# Payload_Development_Kit.net
KiCad netlist of a schematic drawn in Altium Designer
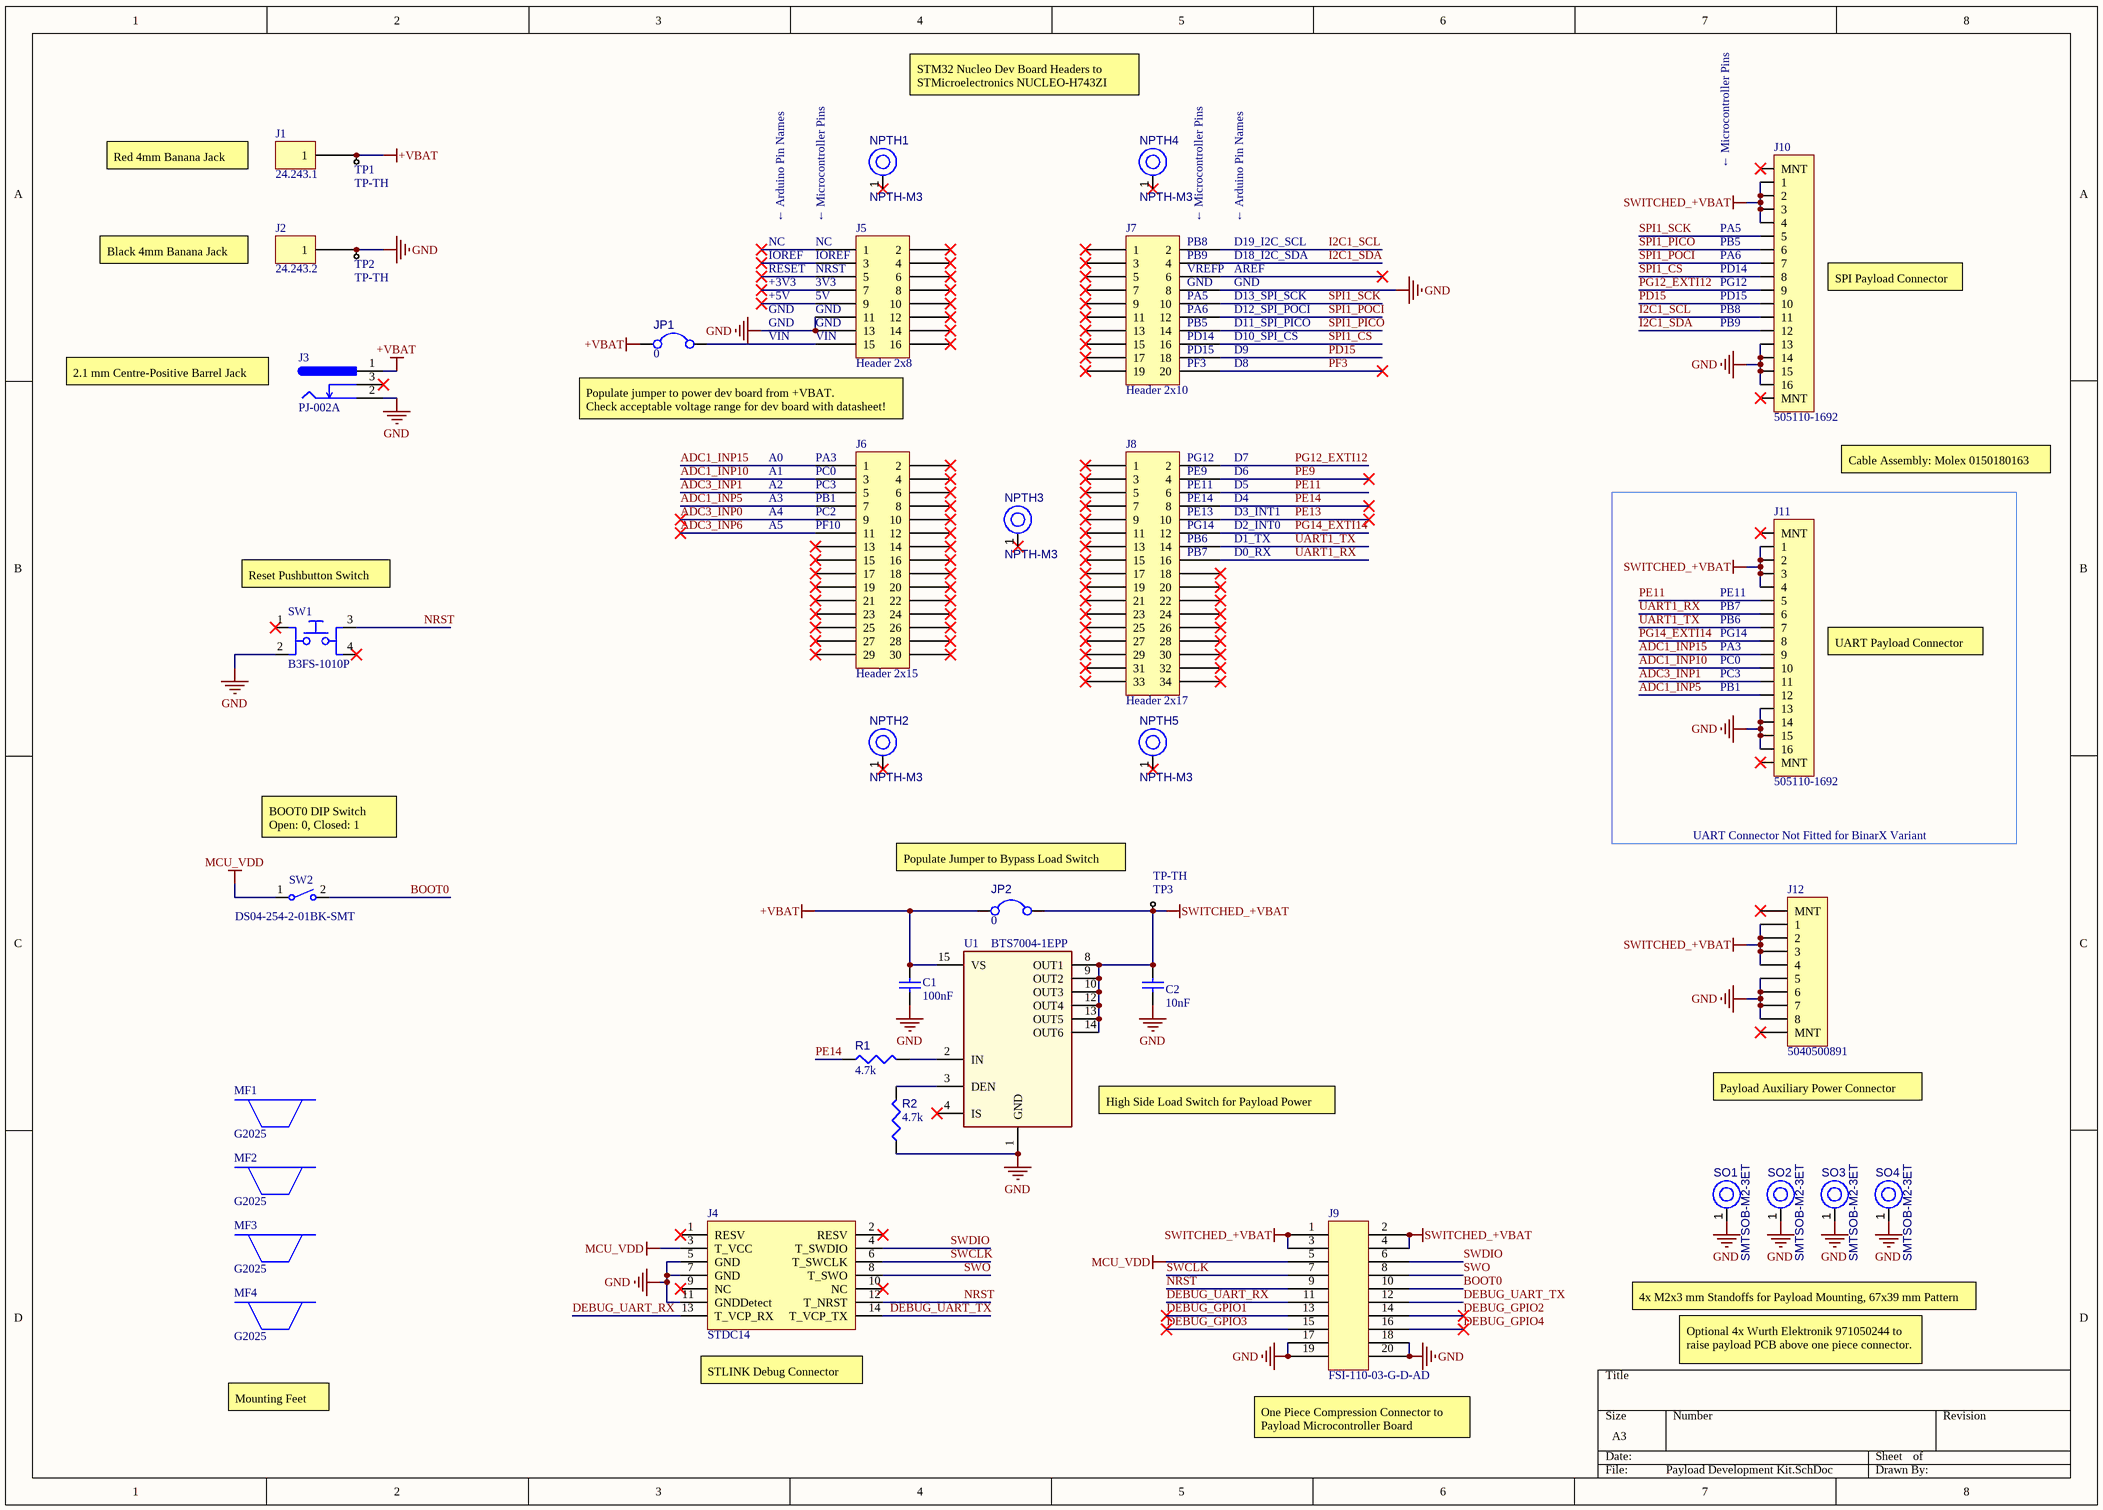
[diagram p0: Payload Development Kit.SchDoc]

(export (version "E")
  (design (tool "Eeschema 10.0.6"))
  (components
    (comp (ref "C1")
      (value "100nF")
      (footprint "CAPC1608X90X40ML10T20")
      (description "Chip Capacitor, 100 nF, +/- 10%, 50 V, 0603 (1608 Metric)")
      (fields (field (name "TOLERANCE") "10%") (field (name "Comment") "Capacitor 100 nF +/-10% 50 V 0603"))
      (libsource (lib "Binar Space Program - Curtin University") (part "CAP-NP-2"))
    )
    (comp (ref "C2")
      (value "10nF")
      (footprint "CAPC1608X90X40NL10T20")
      (description "Chip Capacitor, 10 nF, +/- 10%, 50 V, 0603 (1608 Metric)")
      (fields
        (field (name "TOLERANCE") "10%")
        (field (name "Comment") "Capacitor 10 nF +/-10% 50 V 0603")
        (field (name "CREATED BY") "Robert Howie")
      )
      (libsource (lib "Binar Space Program - Curtin University") (part "CAP-NP-2"))
    )
    (comp (ref "J1")
      (value "24.243.1")
      (footprint "FP-24_243_1-MFG")
      (description "Banana Test Connector, 4mm, Socket, PCB Mount, 24 A, 60 VDC, Silver Plated Contacts, Red")
      (fields (field (name "SOURCE") "Spacecraft Emulator Nucleo-144 Shield.SCHLIB"))
      (libsource (lib "Binar Space Program - Curtin University") (part "24.243.1"))
    )
    (comp (ref "J2")
      (value "24.243.2")
      (footprint "FP-24_243_2-MFG")
      (description "Banana Test Connector, 4mm, Socket, PCB Mount, 24 A, 60 VDC, Silver Plated Contacts, Black")
      (fields (field (name "SOURCE") "Spacecraft Emulator Nucleo-144 Shield.SCHLIB"))
      (libsource (lib "Binar Space Program - Curtin University") (part "24.243.2"))
    )
    (comp (ref "J3")
      (value "PJ-002A")
      (footprint "CUI-PJ-002A_V")
      (description "2.1mm Dia Centre Pin, 5.5mm barrel, 24V, 2.5A")
      (libsource (lib "Binar Space Program - Curtin University") (part "Barrel Jack with NC Insertion Switch"))
    )
    (comp (ref "J4")
      (value "STDC14")
      (footprint "FP-FTSH-107-01-L-DV-K")
      (description "STDC14 for STLINK Programmer")
      (libsource (lib "Binar Space Program - Curtin University") (part "STDC14"))
    )
    (comp (ref "J5")
      (value "Header 2x8")
      (footprint "SAMTEC_SSW-108-01-T-D")
      (fields (field (name "SOURCE") "Spacecraft Emulator Nucleo-144 Shield.SCHLIB"))
      (libsource (lib "Binar Space Program - Curtin University") (part "CMP-002-00019-12"))
    )
    (comp (ref "J6")
      (value "Header 2x15")
      (footprint "SAMTEC_SSW-115-01-T-D")
      (fields (field (name "SOURCE") "Spacecraft Emulator Nucleo-144 Shield.SCHLIB"))
      (libsource (lib "Binar Space Program - Curtin University") (part "CMP-002-00020-6"))
    )
    (comp (ref "J7")
      (value "Header 2x10")
      (footprint "SAMTEC_SSW-110-01-T-D")
      (fields (field (name "SOURCE") "Spacecraft Emulator Nucleo-144 Shield.SCHLIB"))
      (libsource (lib "Binar Space Program - Curtin University") (part "CMP-002-00021-9"))
    )
    (comp (ref "J8")
      (value "Header 2x17")
      (footprint "SAMTEC_SSW-117-01-T-D")
      (fields (field (name "SOURCE") "Spacecraft Emulator Nucleo-144 Shield.SCHLIB"))
      (libsource (lib "Binar Space Program - Curtin University") (part "CMP-002-00022-6"))
    )
    (comp (ref "J9")
      (value "FSI-110-03-G-D-AD")
      (footprint "SAMTEC_FSI-110-03-X-D-AD-TR")
      (description "20 Position, 2 Row, 1mm Pich One Piece Connector, SMD, Samtec FSI-110-03-G-D-AD")
      (libsource (lib "Binar Space Program - Curtin University") (part "CMP-002-00071-3"))
    )
    (comp (ref "J10")
      (value "505110-1692")
      (footprint "FP-505110-1692-MFG")
      (description "Conn FFC/FPC Connector SKT 16 POS 0.5mm Solder RA SMD Easy-On™ T/R")
      (fields (field (name "SOURCE") "Spacecraft Emulator Nucleo-144 Shield.SCHLIB"))
      (libsource (lib "Binar Space Program - Curtin University") (part "CMP-002-00072-15"))
    )
    (comp (ref "J11")
      (value "505110-1692")
      (footprint "FP-505110-1692-MFG")
      (description "Conn FFC/FPC Connector SKT 16 POS 0.5mm Solder RA SMD Easy-On™ T/R")
      (fields (field (name "SOURCE") "Spacecraft Emulator Nucleo-144 Shield.SCHLIB"))
      (libsource (lib "Binar Space Program - Curtin University") (part "CMP-002-00072-15"))
    )
    (comp (ref "J12")
      (value "5040500891")
      (footprint "CON_5040500891")
      (libsource (lib "Binar Space Program - Curtin University") (part "CMP-002-00075-1"))
    )
    (comp (ref "JP1")
      (value "0")
      (footprint "RESC1608X55X25ML10T15")
      (description "Jumper 0603")
      (fields (field (name "Comment") "CMP-009-00177-3"))
      (libsource (lib "Binar Space Program - Curtin University") (part "CMP-009-00177-3"))
    )
    (comp (ref "JP2")
      (value "0")
      (footprint "RESC1608X55X25ML10T15")
      (description "28A Jumper 0603")
      (fields (field (name "Comment") "26A 0603 Jumper"))
      (libsource (lib "Binar Space Program - Curtin University") (part "CMP-009-00177-3"))
    )
    (comp (ref "MF1")
      (value "G2025")
      (footprint "New footprint 1")
      (description "Rubber Push-In Bumper Ø12.7 mm by 12.7 mm high")
      (libsource (lib "Binar Space Program - Curtin University") (part "New symbol 1"))
    )
    (comp (ref "MF2")
      (value "G2025")
      (footprint "New footprint 1")
      (description "Rubber Push-In Bumper Ø12.7 mm by 12.7 mm high")
      (libsource (lib "Binar Space Program - Curtin University") (part "New symbol 1"))
    )
    (comp (ref "MF3")
      (value "G2025")
      (footprint "New footprint 1")
      (description "Rubber Push-In Bumper Ø12.7 mm by 12.7 mm high")
      (libsource (lib "Binar Space Program - Curtin University") (part "New symbol 1"))
    )
    (comp (ref "MF4")
      (value "G2025")
      (footprint "New footprint 1")
      (description "Rubber Push-In Bumper Ø12.7 mm by 12.7 mm high")
      (libsource (lib "Binar Space Program - Curtin University") (part "New symbol 1"))
    )
    (comp (ref "NPTH1")
      (value "NPTH-M3")
      (footprint "NPTH-M3")
      (description "M3 Non-Plated Through Hole")
      (fields (field (name "SOURCE") "Spacecraft Emulator Nucleo-144 Shield.SCHLIB"))
      (libsource (lib "Binar Space Program - Curtin University") (part "CMP-00028-00015-4"))
    )
    (comp (ref "NPTH2")
      (value "NPTH-M3")
      (footprint "NPTH-M3")
      (description "M3 Non-Plated Through Hole")
      (fields (field (name "SOURCE") "Spacecraft Emulator Nucleo-144 Shield.SCHLIB"))
      (libsource (lib "Binar Space Program - Curtin University") (part "CMP-00028-00015-4"))
    )
    (comp (ref "NPTH3")
      (value "NPTH-M3")
      (footprint "NPTH-M3")
      (description "M3 Non-Plated Through Hole")
      (fields (field (name "SOURCE") "Spacecraft Emulator Nucleo-144 Shield.SCHLIB"))
      (libsource (lib "Binar Space Program - Curtin University") (part "CMP-00028-00015-4"))
    )
    (comp (ref "NPTH4")
      (value "NPTH-M3")
      (footprint "NPTH-M3")
      (description "M3 Non-Plated Through Hole")
      (fields (field (name "SOURCE") "Spacecraft Emulator Nucleo-144 Shield.SCHLIB"))
      (libsource (lib "Binar Space Program - Curtin University") (part "CMP-00028-00015-4"))
    )
    (comp (ref "NPTH5")
      (value "NPTH-M3")
      (footprint "NPTH-M3")
      (description "M3 Non-Plated Through Hole")
      (fields (field (name "SOURCE") "Spacecraft Emulator Nucleo-144 Shield.SCHLIB"))
      (libsource (lib "Binar Space Program - Curtin University") (part "CMP-00028-00015-4"))
    )
    (comp (ref "R1")
      (value "4.7k")
      (footprint "RESC1608X55X25ML10T15")
      (description "Chip Resistor, 4.7 KOhm, +/- 1%, 0.1 W, -55 to 155 degC, 0603 (1608 Metric)")
      (fields
        (field (name "TOLERANCE") "1%")
        (field (name "POWER") "100mW")
        (field (name "CREATED BY") "Robert Howie")
      )
      (libsource (lib "Binar Space Program - Curtin University") (part "RES-2"))
    )
    (comp (ref "R2")
      (value "4.7k")
      (footprint "RESC1608X55X25ML10T15")
      (description "Chip Resistor, 4.7 KOhm, +/- 1%, 0.1 W, -55 to 155 degC, 0603 (1608 Metric)")
      (fields
        (field (name "TOLERANCE") "1%")
        (field (name "POWER") "100mW")
        (field (name "CREATED BY") "Robert Howie")
      )
      (libsource (lib "Binar Space Program - Curtin University") (part "RES-2"))
    )
    (comp (ref "SO1")
      (value "SMTSOB-M2-3ET")
      (footprint "SMTSOB-M2-3ET")
      (description "M2x3mm SMD Standoff, Brass")
      (libsource (lib "Binar Space Program - Curtin University") (part "CMP-00028-00008-1"))
    )
    (comp (ref "SO2")
      (value "SMTSOB-M2-3ET")
      (footprint "SMTSOB-M2-3ET")
      (description "M2x3mm SMD Standoff, Brass")
      (libsource (lib "Binar Space Program - Curtin University") (part "CMP-00028-00008-1"))
    )
    (comp (ref "SO3")
      (value "SMTSOB-M2-3ET")
      (footprint "SMTSOB-M2-3ET")
      (description "M2x3mm SMD Standoff, Brass")
      (libsource (lib "Binar Space Program - Curtin University") (part "CMP-00028-00008-1"))
    )
    (comp (ref "SO4")
      (value "SMTSOB-M2-3ET")
      (footprint "SMTSOB-M2-3ET")
      (description "M2x3mm SMD Standoff, Brass")
      (libsource (lib "Binar Space Program - Curtin University") (part "CMP-00028-00008-1"))
    )
    (comp (ref "SW1")
      (value "B3FS-1010P")
      (footprint "B3FS-1010P-Footprint-1")
      (libsource (lib "Binar Space Program - Curtin University") (part "SW-SPST-NO-4"))
    )
    (comp (ref "SW2")
      (value "DS04-254-2-01BK-SMT")
      (footprint "SW_DS04-254-1-01BK-SMT")
      (description "DIP Switch")
      (libsource (lib "Binar Space Program - Curtin University") (part "SW-SPST-2_C"))
    )
    (comp (ref "TP1")
      (value "TP-TH")
      (footprint "1 Pin Header Strip Footprint")
      (description "Throughole Test Point")
      (fields (field (name "CREATED BY") "Robert Howie"))
      (libsource (lib "Binar Space Program - Curtin University") (part "CMP-001-0001-5"))
    )
    (comp (ref "TP2")
      (value "TP-TH")
      (footprint "1 Pin Header Strip Footprint")
      (description "Throughole Test Point")
      (fields (field (name "CREATED BY") "Robert Howie"))
      (libsource (lib "Binar Space Program - Curtin University") (part "CMP-001-0001-5"))
    )
    (comp (ref "TP3")
      (value "TP-TH")
      (footprint "1 Pin Header Strip Footprint")
      (description "Throughole Test Point")
      (fields (field (name "CREATED BY") "Robert Howie"))
      (libsource (lib "Binar Space Program - Curtin University") (part "CMP-001-0001-5"))
    )
    (comp (ref "U1")
      (value "BTS7004-1EPP")
      (footprint "SOP65P600X105-15N-1-V")
      (description "Smart High-Side Power Switch, 1x4 mΩ")
      (fields (field (name "MANUFACTURER") "Infineon Technologies"))
      (libsource (lib "Binar Space Program - Curtin University") (part "BTS7004-1EPP"))
    )
  )
  (nets
    (net (code "1") (name "+VBAT") (class "Default")
      (node (ref "C1") (pin "1") (pinfunction "1_1") (pintype "passive"))
      (node (ref "J1") (pin "1") (pinfunction "1_1") (pintype "passive"))
      (node (ref "J1") (pin "2") (pinfunction "2_2") (pintype "passive"))
      (node (ref "J3") (pin "1") (pinfunction "1_1") (pintype "passive"))
      (node (ref "JP1") (pin "1") (pinfunction "1_1") (pintype "passive"))
      (node (ref "JP2") (pin "1") (pinfunction "1_1") (pintype "passive"))
      (node (ref "TP1") (pin "1") (pinfunction "TP_1") (pintype "passive"))
      (node (ref "U1") (pin "15") (pinfunction "VS_15") (pintype "passive"))
    )
    (net (code "2") (name "/ADC1_INP5") (class "Default")
      (node (ref "J11") (pin "12") (pinfunction "12_12") (pintype "passive"))
      (node (ref "J6") (pin "7") (pinfunction "7_7") (pintype "passive"))
    )
    (net (code "3") (name "/ADC1_INP10") (class "Default")
      (node (ref "J11") (pin "10") (pinfunction "10_10") (pintype "passive"))
      (node (ref "J6") (pin "3") (pinfunction "3_3") (pintype "passive"))
    )
    (net (code "4") (name "/ADC1_INP15") (class "Default")
      (node (ref "J11") (pin "9") (pinfunction "9_9") (pintype "passive"))
      (node (ref "J6") (pin "1") (pinfunction "1_1") (pintype "passive"))
    )
    (net (code "5") (name "/ADC3_INP0") (class "Default")
      (node (ref "J6") (pin "9") (pinfunction "9_9") (pintype "passive+no_connect"))
    )
    (net (code "6") (name "/ADC3_INP1") (class "Default")
      (node (ref "J11") (pin "11") (pinfunction "11_11") (pintype "passive"))
      (node (ref "J6") (pin "5") (pinfunction "5_5") (pintype "passive"))
    )
    (net (code "7") (name "/ADC3_INP6") (class "Default")
      (node (ref "J6") (pin "11") (pinfunction "11_11") (pintype "passive+no_connect"))
    )
    (net (code "8") (name "/BOOT0") (class "Default")
      (node (ref "J9") (pin "10") (pinfunction "10_10") (pintype "passive"))
      (node (ref "SW2") (pin "2") (pinfunction "2_2") (pintype "passive"))
    )
    (net (code "9") (name "/DEBUG_GPIO1") (class "Default")
      (node (ref "J9") (pin "13") (pinfunction "13_13") (pintype "passive+no_connect"))
    )
    (net (code "10") (name "/DEBUG_GPIO2") (class "Default")
      (node (ref "J9") (pin "14") (pinfunction "14_14") (pintype "passive+no_connect"))
    )
    (net (code "11") (name "/DEBUG_GPIO3") (class "Default")
      (node (ref "J9") (pin "15") (pinfunction "15_15") (pintype "passive+no_connect"))
    )
    (net (code "12") (name "/DEBUG_GPIO4") (class "Default")
      (node (ref "J9") (pin "16") (pinfunction "16_16") (pintype "passive+no_connect"))
    )
    (net (code "13") (name "/DEBUG_UART_RX") (class "Default")
      (node (ref "J4") (pin "13") (pinfunction "T_VCP_RX_13") (pintype "passive"))
      (node (ref "J9") (pin "11") (pinfunction "11_11") (pintype "passive"))
    )
    (net (code "14") (name "/DEBUG_UART_TX") (class "Default")
      (node (ref "J4") (pin "14") (pinfunction "T_VCP_TX_14") (pintype "passive"))
      (node (ref "J9") (pin "12") (pinfunction "12_12") (pintype "passive"))
    )
    (net (code "15") (name "/I2C1_SCL") (class "Default")
      (node (ref "J10") (pin "11") (pinfunction "11_11") (pintype "passive"))
      (node (ref "J7") (pin "2") (pinfunction "2_2") (pintype "passive"))
    )
    (net (code "16") (name "/I2C1_SDA") (class "Default")
      (node (ref "J10") (pin "12") (pinfunction "12_12") (pintype "passive"))
      (node (ref "J7") (pin "4") (pinfunction "4_4") (pintype "passive"))
    )
    (net (code "17") (name "/NRST") (class "Default")
      (node (ref "J4") (pin "12") (pinfunction "T_NRST_12") (pintype "passive"))
      (node (ref "J9") (pin "9") (pinfunction "9_9") (pintype "passive"))
      (node (ref "SW1") (pin "3") (pinfunction "3_3") (pintype "passive"))
    )
    (net (code "18") (name "/PD15") (class "Default")
      (node (ref "J10") (pin "10") (pinfunction "10_10") (pintype "passive"))
      (node (ref "J7") (pin "18") (pinfunction "18_18") (pintype "passive"))
    )
    (net (code "19") (name "/PE9") (class "Default")
      (node (ref "J8") (pin "4") (pinfunction "4_4") (pintype "passive+no_connect"))
    )
    (net (code "20") (name "/PE11") (class "Default")
      (node (ref "J11") (pin "5") (pinfunction "5_5") (pintype "passive"))
      (node (ref "J8") (pin "6") (pinfunction "6_6") (pintype "passive"))
    )
    (net (code "21") (name "/PE13") (class "Default")
      (node (ref "J8") (pin "10") (pinfunction "10_10") (pintype "passive+no_connect"))
    )
    (net (code "22") (name "/PE14") (class "Default")
      (node (ref "J8") (pin "8") (pinfunction "8_8") (pintype "passive"))
      (node (ref "R1") (pin "1") (pinfunction "1_1") (pintype "passive"))
    )
    (net (code "23") (name "/PF3") (class "Default")
      (node (ref "J7") (pin "20") (pinfunction "20_20") (pintype "passive+no_connect"))
    )
    (net (code "24") (name "/PG12_EXTI12") (class "Default")
      (node (ref "J10") (pin "9") (pinfunction "9_9") (pintype "passive"))
      (node (ref "J8") (pin "2") (pinfunction "2_2") (pintype "passive"))
    )
    (net (code "25") (name "/PG14_EXTI14") (class "Default")
      (node (ref "J11") (pin "8") (pinfunction "8_8") (pintype "passive"))
      (node (ref "J8") (pin "12") (pinfunction "12_12") (pintype "passive"))
    )
    (net (code "26") (name "/SPI1_CS") (class "Default")
      (node (ref "J10") (pin "8") (pinfunction "8_8") (pintype "passive"))
      (node (ref "J7") (pin "16") (pinfunction "16_16") (pintype "passive"))
    )
    (net (code "27") (name "/SPI1_PICO") (class "Default")
      (node (ref "J10") (pin "6") (pinfunction "6_6") (pintype "passive"))
      (node (ref "J7") (pin "14") (pinfunction "14_14") (pintype "passive"))
    )
    (net (code "28") (name "/SPI1_POCI") (class "Default")
      (node (ref "J10") (pin "7") (pinfunction "7_7") (pintype "passive"))
      (node (ref "J7") (pin "12") (pinfunction "12_12") (pintype "passive"))
    )
    (net (code "29") (name "/SPI1_SCK") (class "Default")
      (node (ref "J10") (pin "5") (pinfunction "5_5") (pintype "passive"))
      (node (ref "J7") (pin "10") (pinfunction "10_10") (pintype "passive"))
    )
    (net (code "30") (name "/SWCLK") (class "Default")
      (node (ref "J4") (pin "6") (pinfunction "T_SWCLK_6") (pintype "passive"))
      (node (ref "J9") (pin "7") (pinfunction "7_7") (pintype "passive"))
    )
    (net (code "31") (name "/SWDIO") (class "Default")
      (node (ref "J4") (pin "4") (pinfunction "T_SWDIO_4") (pintype "passive"))
      (node (ref "J9") (pin "6") (pinfunction "6_6") (pintype "passive"))
    )
    (net (code "32") (name "/SWO") (class "Default")
      (node (ref "J4") (pin "8") (pinfunction "T_SWO_8") (pintype "passive"))
      (node (ref "J9") (pin "8") (pinfunction "8_8") (pintype "passive"))
    )
    (net (code "33") (name "/UART1_RX") (class "Default")
      (node (ref "J11") (pin "6") (pinfunction "6_6") (pintype "passive"))
      (node (ref "J8") (pin "16") (pinfunction "16_16") (pintype "passive"))
    )
    (net (code "34") (name "/UART1_TX") (class "Default")
      (node (ref "J11") (pin "7") (pinfunction "7_7") (pintype "passive"))
      (node (ref "J8") (pin "14") (pinfunction "14_14") (pintype "passive"))
    )
    (net (code "35") (name "GND") (class "Default")
      (node (ref "C1") (pin "2") (pinfunction "2_2") (pintype "passive"))
      (node (ref "C2") (pin "1") (pinfunction "1_1") (pintype "passive"))
      (node (ref "J10") (pin "13") (pinfunction "13_13") (pintype "passive"))
      (node (ref "J10") (pin "14") (pinfunction "14_14") (pintype "passive"))
      (node (ref "J10") (pin "15") (pinfunction "15_15") (pintype "passive"))
      (node (ref "J10") (pin "16") (pinfunction "16_16") (pintype "passive"))
      (node (ref "J11") (pin "13") (pinfunction "13_13") (pintype "passive"))
      (node (ref "J11") (pin "14") (pinfunction "14_14") (pintype "passive"))
      (node (ref "J11") (pin "15") (pinfunction "15_15") (pintype "passive"))
      (node (ref "J11") (pin "16") (pinfunction "16_16") (pintype "passive"))
      (node (ref "J12") (pin "5") (pinfunction "5_5") (pintype "passive"))
      (node (ref "J12") (pin "6") (pinfunction "6_6") (pintype "passive"))
      (node (ref "J12") (pin "7") (pinfunction "7_7") (pintype "passive"))
      (node (ref "J12") (pin "8") (pinfunction "8_8") (pintype "passive"))
      (node (ref "J2") (pin "1") (pinfunction "1_1") (pintype "passive"))
      (node (ref "J2") (pin "2") (pinfunction "2_2") (pintype "passive"))
      (node (ref "J3") (pin "2") (pinfunction "2_2") (pintype "passive"))
      (node (ref "J4") (pin "11") (pinfunction "GNDDetect_11") (pintype "passive"))
      (node (ref "J4") (pin "5") (pinfunction "GND_5") (pintype "passive"))
      (node (ref "J4") (pin "7") (pinfunction "GND_7") (pintype "passive"))
      (node (ref "J5") (pin "11") (pinfunction "11_11") (pintype "passive"))
      (node (ref "J5") (pin "13") (pinfunction "13_13") (pintype "passive"))
      (node (ref "J7") (pin "8") (pinfunction "8_8") (pintype "passive"))
      (node (ref "J9") (pin "17") (pinfunction "17_17") (pintype "passive"))
      (node (ref "J9") (pin "18") (pinfunction "18_18") (pintype "passive"))
      (node (ref "J9") (pin "19") (pinfunction "19_19") (pintype "passive"))
      (node (ref "J9") (pin "20") (pinfunction "20_20") (pintype "passive"))
      (node (ref "R2") (pin "1") (pinfunction "1_1") (pintype "passive"))
      (node (ref "SO1") (pin "1") (pinfunction "H1_1") (pintype "passive"))
      (node (ref "SO2") (pin "1") (pinfunction "H1_1") (pintype "passive"))
      (node (ref "SO3") (pin "1") (pinfunction "H1_1") (pintype "passive"))
      (node (ref "SO4") (pin "1") (pinfunction "H1_1") (pintype "passive"))
      (node (ref "SW1") (pin "2") (pinfunction "2_2") (pintype "passive"))
      (node (ref "TP2") (pin "1") (pinfunction "TP_1") (pintype "passive"))
      (node (ref "U1") (pin "1") (pinfunction "GND_1") (pintype "passive"))
    )
    (net (code "36") (name "MCU_VDD") (class "Default")
      (node (ref "J4") (pin "3") (pinfunction "T_VCC_3") (pintype "passive"))
      (node (ref "J9") (pin "5") (pinfunction "5_5") (pintype "passive"))
      (node (ref "SW2") (pin "1") (pinfunction "1_1") (pintype "passive"))
    )
    (net (code "37") (name "Net-(J5-Pad15)") (class "Default")
      (node (ref "J5") (pin "15") (pinfunction "15_15") (pintype "passive"))
      (node (ref "JP1") (pin "2") (pinfunction "2_2") (pintype "passive"))
    )
    (net (code "38") (name "Net-(U1-DEN)") (class "Default")
      (node (ref "R2") (pin "2") (pinfunction "2_2") (pintype "passive"))
      (node (ref "U1") (pin "3") (pinfunction "DEN_3") (pintype "passive"))
    )
    (net (code "39") (name "Net-(U1-IN)") (class "Default")
      (node (ref "R1") (pin "2") (pinfunction "2_2") (pintype "passive"))
      (node (ref "U1") (pin "2") (pinfunction "IN_2") (pintype "passive"))
    )
    (net (code "40") (name "SWITCHED_+VBAT") (class "Default")
      (node (ref "C2") (pin "2") (pinfunction "2_2") (pintype "passive"))
      (node (ref "J10") (pin "1") (pinfunction "1_1") (pintype "passive"))
      (node (ref "J10") (pin "2") (pinfunction "2_2") (pintype "passive"))
      (node (ref "J10") (pin "3") (pinfunction "3_3") (pintype "passive"))
      (node (ref "J10") (pin "4") (pinfunction "4_4") (pintype "passive"))
      (node (ref "J11") (pin "1") (pinfunction "1_1") (pintype "passive"))
      (node (ref "J11") (pin "2") (pinfunction "2_2") (pintype "passive"))
      (node (ref "J11") (pin "3") (pinfunction "3_3") (pintype "passive"))
      (node (ref "J11") (pin "4") (pinfunction "4_4") (pintype "passive"))
      (node (ref "J12") (pin "1") (pinfunction "1_1") (pintype "passive"))
      (node (ref "J12") (pin "2") (pinfunction "2_2") (pintype "passive"))
      (node (ref "J12") (pin "3") (pinfunction "3_3") (pintype "passive"))
      (node (ref "J12") (pin "4") (pinfunction "4_4") (pintype "passive"))
      (node (ref "J9") (pin "1") (pinfunction "1_1") (pintype "passive"))
      (node (ref "J9") (pin "2") (pinfunction "2_2") (pintype "passive"))
      (node (ref "J9") (pin "3") (pinfunction "3_3") (pintype "passive"))
      (node (ref "J9") (pin "4") (pinfunction "4_4") (pintype "passive"))
      (node (ref "JP2") (pin "2") (pinfunction "2_2") (pintype "passive"))
      (node (ref "TP3") (pin "1") (pinfunction "TP_1") (pintype "passive"))
      (node (ref "U1") (pin "10") (pinfunction "OUT3_10") (pintype "passive"))
      (node (ref "U1") (pin "12") (pinfunction "OUT4_12") (pintype "passive"))
      (node (ref "U1") (pin "13") (pinfunction "OUT5_13") (pintype "passive"))
      (node (ref "U1") (pin "14") (pinfunction "OUT6_14") (pintype "passive"))
      (node (ref "U1") (pin "8") (pinfunction "OUT1_8") (pintype "passive"))
      (node (ref "U1") (pin "9") (pinfunction "OUT2_9") (pintype "passive"))
    )
    (net (code "41") (name "unconnected-(J3-Pad3)") (class "Default")
      (node (ref "J3") (pin "3") (pinfunction "3_3") (pintype "passive+no_connect"))
    )
    (net (code "42") (name "unconnected-(J4-NC-Pad9)") (class "Default")
      (node (ref "J4") (pin "9") (pinfunction "NC_9") (pintype "passive+no_connect"))
    )
    (net (code "43") (name "unconnected-(J4-NC-Pad10)") (class "Default")
      (node (ref "J4") (pin "10") (pinfunction "NC_10") (pintype "passive+no_connect"))
    )
    (net (code "44") (name "unconnected-(J4-RESV-Pad1)") (class "Default")
      (node (ref "J4") (pin "1") (pinfunction "RESV_1") (pintype "passive+no_connect"))
    )
    (net (code "45") (name "unconnected-(J4-RESV-Pad2)") (class "Default")
      (node (ref "J4") (pin "2") (pinfunction "RESV_2") (pintype "passive+no_connect"))
    )
    (net (code "46") (name "unconnected-(J5-Pad1)") (class "Default")
      (node (ref "J5") (pin "1") (pinfunction "1_1") (pintype "passive+no_connect"))
    )
    (net (code "47") (name "unconnected-(J5-Pad2)") (class "Default")
      (node (ref "J5") (pin "2") (pinfunction "2_2") (pintype "passive+no_connect"))
    )
    (net (code "48") (name "unconnected-(J5-Pad3)") (class "Default")
      (node (ref "J5") (pin "3") (pinfunction "3_3") (pintype "passive+no_connect"))
    )
    (net (code "49") (name "unconnected-(J5-Pad4)") (class "Default")
      (node (ref "J5") (pin "4") (pinfunction "4_4") (pintype "passive+no_connect"))
    )
    (net (code "50") (name "unconnected-(J5-Pad5)") (class "Default")
      (node (ref "J5") (pin "5") (pinfunction "5_5") (pintype "passive+no_connect"))
    )
    (net (code "51") (name "unconnected-(J5-Pad6)") (class "Default")
      (node (ref "J5") (pin "6") (pinfunction "6_6") (pintype "passive+no_connect"))
    )
    (net (code "52") (name "unconnected-(J5-Pad7)") (class "Default")
      (node (ref "J5") (pin "7") (pinfunction "7_7") (pintype "passive+no_connect"))
    )
    (net (code "53") (name "unconnected-(J5-Pad8)") (class "Default")
      (node (ref "J5") (pin "8") (pinfunction "8_8") (pintype "passive+no_connect"))
    )
    (net (code "54") (name "unconnected-(J5-Pad9)") (class "Default")
      (node (ref "J5") (pin "9") (pinfunction "9_9") (pintype "passive+no_connect"))
    )
    (net (code "55") (name "unconnected-(J5-Pad10)") (class "Default")
      (node (ref "J5") (pin "10") (pinfunction "10_10") (pintype "passive+no_connect"))
    )
    (net (code "56") (name "unconnected-(J5-Pad12)") (class "Default")
      (node (ref "J5") (pin "12") (pinfunction "12_12") (pintype "passive+no_connect"))
    )
    (net (code "57") (name "unconnected-(J5-Pad14)") (class "Default")
      (node (ref "J5") (pin "14") (pinfunction "14_14") (pintype "passive+no_connect"))
    )
    (net (code "58") (name "unconnected-(J5-Pad16)") (class "Default")
      (node (ref "J5") (pin "16") (pinfunction "16_16") (pintype "passive+no_connect"))
    )
    (net (code "59") (name "unconnected-(J6-Pad2)") (class "Default")
      (node (ref "J6") (pin "2") (pinfunction "2_2") (pintype "passive+no_connect"))
    )
    (net (code "60") (name "unconnected-(J6-Pad4)") (class "Default")
      (node (ref "J6") (pin "4") (pinfunction "4_4") (pintype "passive+no_connect"))
    )
    (net (code "61") (name "unconnected-(J6-Pad6)") (class "Default")
      (node (ref "J6") (pin "6") (pinfunction "6_6") (pintype "passive+no_connect"))
    )
    (net (code "62") (name "unconnected-(J6-Pad8)") (class "Default")
      (node (ref "J6") (pin "8") (pinfunction "8_8") (pintype "passive+no_connect"))
    )
    (net (code "63") (name "unconnected-(J6-Pad10)") (class "Default")
      (node (ref "J6") (pin "10") (pinfunction "10_10") (pintype "passive+no_connect"))
    )
    (net (code "64") (name "unconnected-(J6-Pad12)") (class "Default")
      (node (ref "J6") (pin "12") (pinfunction "12_12") (pintype "passive+no_connect"))
    )
    (net (code "65") (name "unconnected-(J6-Pad13)") (class "Default")
      (node (ref "J6") (pin "13") (pinfunction "13_13") (pintype "passive+no_connect"))
    )
    (net (code "66") (name "unconnected-(J6-Pad14)") (class "Default")
      (node (ref "J6") (pin "14") (pinfunction "14_14") (pintype "passive+no_connect"))
    )
    (net (code "67") (name "unconnected-(J6-Pad15)") (class "Default")
      (node (ref "J6") (pin "15") (pinfunction "15_15") (pintype "passive+no_connect"))
    )
    (net (code "68") (name "unconnected-(J6-Pad16)") (class "Default")
      (node (ref "J6") (pin "16") (pinfunction "16_16") (pintype "passive+no_connect"))
    )
    (net (code "69") (name "unconnected-(J6-Pad17)") (class "Default")
      (node (ref "J6") (pin "17") (pinfunction "17_17") (pintype "passive+no_connect"))
    )
    (net (code "70") (name "unconnected-(J6-Pad18)") (class "Default")
      (node (ref "J6") (pin "18") (pinfunction "18_18") (pintype "passive+no_connect"))
    )
    (net (code "71") (name "unconnected-(J6-Pad19)") (class "Default")
      (node (ref "J6") (pin "19") (pinfunction "19_19") (pintype "passive+no_connect"))
    )
    (net (code "72") (name "unconnected-(J6-Pad20)") (class "Default")
      (node (ref "J6") (pin "20") (pinfunction "20_20") (pintype "passive+no_connect"))
    )
    (net (code "73") (name "unconnected-(J6-Pad21)") (class "Default")
      (node (ref "J6") (pin "21") (pinfunction "21_21") (pintype "passive+no_connect"))
    )
    (net (code "74") (name "unconnected-(J6-Pad22)") (class "Default")
      (node (ref "J6") (pin "22") (pinfunction "22_22") (pintype "passive+no_connect"))
    )
    (net (code "75") (name "unconnected-(J6-Pad23)") (class "Default")
      (node (ref "J6") (pin "23") (pinfunction "23_23") (pintype "passive+no_connect"))
    )
    (net (code "76") (name "unconnected-(J6-Pad24)") (class "Default")
      (node (ref "J6") (pin "24") (pinfunction "24_24") (pintype "passive+no_connect"))
    )
    (net (code "77") (name "unconnected-(J6-Pad25)") (class "Default")
      (node (ref "J6") (pin "25") (pinfunction "25_25") (pintype "passive+no_connect"))
    )
    (net (code "78") (name "unconnected-(J6-Pad26)") (class "Default")
      (node (ref "J6") (pin "26") (pinfunction "26_26") (pintype "passive+no_connect"))
    )
    (net (code "79") (name "unconnected-(J6-Pad27)") (class "Default")
      (node (ref "J6") (pin "27") (pinfunction "27_27") (pintype "passive+no_connect"))
    )
    (net (code "80") (name "unconnected-(J6-Pad28)") (class "Default")
      (node (ref "J6") (pin "28") (pinfunction "28_28") (pintype "passive+no_connect"))
    )
    (net (code "81") (name "unconnected-(J6-Pad29)") (class "Default")
      (node (ref "J6") (pin "29") (pinfunction "29_29") (pintype "passive+no_connect"))
    )
    (net (code "82") (name "unconnected-(J6-Pad30)") (class "Default")
      (node (ref "J6") (pin "30") (pinfunction "30_30") (pintype "passive+no_connect"))
    )
    (net (code "83") (name "unconnected-(J7-Pad1)") (class "Default")
      (node (ref "J7") (pin "1") (pinfunction "1_1") (pintype "passive+no_connect"))
    )
    (net (code "84") (name "unconnected-(J7-Pad3)") (class "Default")
      (node (ref "J7") (pin "3") (pinfunction "3_3") (pintype "passive+no_connect"))
    )
    (net (code "85") (name "unconnected-(J7-Pad5)") (class "Default")
      (node (ref "J7") (pin "5") (pinfunction "5_5") (pintype "passive+no_connect"))
    )
    (net (code "86") (name "unconnected-(J7-Pad6)") (class "Default")
      (node (ref "J7") (pin "6") (pinfunction "6_6") (pintype "passive+no_connect"))
    )
    (net (code "87") (name "unconnected-(J7-Pad7)") (class "Default")
      (node (ref "J7") (pin "7") (pinfunction "7_7") (pintype "passive+no_connect"))
    )
    (net (code "88") (name "unconnected-(J7-Pad9)") (class "Default")
      (node (ref "J7") (pin "9") (pinfunction "9_9") (pintype "passive+no_connect"))
    )
    (net (code "89") (name "unconnected-(J7-Pad11)") (class "Default")
      (node (ref "J7") (pin "11") (pinfunction "11_11") (pintype "passive+no_connect"))
    )
    (net (code "90") (name "unconnected-(J7-Pad13)") (class "Default")
      (node (ref "J7") (pin "13") (pinfunction "13_13") (pintype "passive+no_connect"))
    )
    (net (code "91") (name "unconnected-(J7-Pad15)") (class "Default")
      (node (ref "J7") (pin "15") (pinfunction "15_15") (pintype "passive+no_connect"))
    )
    (net (code "92") (name "unconnected-(J7-Pad17)") (class "Default")
      (node (ref "J7") (pin "17") (pinfunction "17_17") (pintype "passive+no_connect"))
    )
    (net (code "93") (name "unconnected-(J7-Pad19)") (class "Default")
      (node (ref "J7") (pin "19") (pinfunction "19_19") (pintype "passive+no_connect"))
    )
    (net (code "94") (name "unconnected-(J8-Pad1)") (class "Default")
      (node (ref "J8") (pin "1") (pinfunction "1_1") (pintype "passive+no_connect"))
    )
    (net (code "95") (name "unconnected-(J8-Pad3)") (class "Default")
      (node (ref "J8") (pin "3") (pinfunction "3_3") (pintype "passive+no_connect"))
    )
    (net (code "96") (name "unconnected-(J8-Pad5)") (class "Default")
      (node (ref "J8") (pin "5") (pinfunction "5_5") (pintype "passive+no_connect"))
    )
    (net (code "97") (name "unconnected-(J8-Pad7)") (class "Default")
      (node (ref "J8") (pin "7") (pinfunction "7_7") (pintype "passive+no_connect"))
    )
    (net (code "98") (name "unconnected-(J8-Pad9)") (class "Default")
      (node (ref "J8") (pin "9") (pinfunction "9_9") (pintype "passive+no_connect"))
    )
    (net (code "99") (name "unconnected-(J8-Pad11)") (class "Default")
      (node (ref "J8") (pin "11") (pinfunction "11_11") (pintype "passive+no_connect"))
    )
    (net (code "100") (name "unconnected-(J8-Pad13)") (class "Default")
      (node (ref "J8") (pin "13") (pinfunction "13_13") (pintype "passive+no_connect"))
    )
    (net (code "101") (name "unconnected-(J8-Pad15)") (class "Default")
      (node (ref "J8") (pin "15") (pinfunction "15_15") (pintype "passive+no_connect"))
    )
    (net (code "102") (name "unconnected-(J8-Pad17)") (class "Default")
      (node (ref "J8") (pin "17") (pinfunction "17_17") (pintype "passive+no_connect"))
    )
    (net (code "103") (name "unconnected-(J8-Pad18)") (class "Default")
      (node (ref "J8") (pin "18") (pinfunction "18_18") (pintype "passive+no_connect"))
    )
    (net (code "104") (name "unconnected-(J8-Pad19)") (class "Default")
      (node (ref "J8") (pin "19") (pinfunction "19_19") (pintype "passive+no_connect"))
    )
    (net (code "105") (name "unconnected-(J8-Pad20)") (class "Default")
      (node (ref "J8") (pin "20") (pinfunction "20_20") (pintype "passive+no_connect"))
    )
    (net (code "106") (name "unconnected-(J8-Pad21)") (class "Default")
      (node (ref "J8") (pin "21") (pinfunction "21_21") (pintype "passive+no_connect"))
    )
    (net (code "107") (name "unconnected-(J8-Pad22)") (class "Default")
      (node (ref "J8") (pin "22") (pinfunction "22_22") (pintype "passive+no_connect"))
    )
    (net (code "108") (name "unconnected-(J8-Pad23)") (class "Default")
      (node (ref "J8") (pin "23") (pinfunction "23_23") (pintype "passive+no_connect"))
    )
    (net (code "109") (name "unconnected-(J8-Pad24)") (class "Default")
      (node (ref "J8") (pin "24") (pinfunction "24_24") (pintype "passive+no_connect"))
    )
    (net (code "110") (name "unconnected-(J8-Pad25)") (class "Default")
      (node (ref "J8") (pin "25") (pinfunction "25_25") (pintype "passive+no_connect"))
    )
    (net (code "111") (name "unconnected-(J8-Pad26)") (class "Default")
      (node (ref "J8") (pin "26") (pinfunction "26_26") (pintype "passive+no_connect"))
    )
    (net (code "112") (name "unconnected-(J8-Pad27)") (class "Default")
      (node (ref "J8") (pin "27") (pinfunction "27_27") (pintype "passive+no_connect"))
    )
    (net (code "113") (name "unconnected-(J8-Pad28)") (class "Default")
      (node (ref "J8") (pin "28") (pinfunction "28_28") (pintype "passive+no_connect"))
    )
    (net (code "114") (name "unconnected-(J8-Pad29)") (class "Default")
      (node (ref "J8") (pin "29") (pinfunction "29_29") (pintype "passive+no_connect"))
    )
    (net (code "115") (name "unconnected-(J8-Pad30)") (class "Default")
      (node (ref "J8") (pin "30") (pinfunction "30_30") (pintype "passive+no_connect"))
    )
    (net (code "116") (name "unconnected-(J8-Pad31)") (class "Default")
      (node (ref "J8") (pin "31") (pinfunction "31_31") (pintype "passive+no_connect"))
    )
    (net (code "117") (name "unconnected-(J8-Pad32)") (class "Default")
      (node (ref "J8") (pin "32") (pinfunction "32_32") (pintype "passive+no_connect"))
    )
    (net (code "118") (name "unconnected-(J8-Pad33)") (class "Default")
      (node (ref "J8") (pin "33") (pinfunction "33_33") (pintype "passive+no_connect"))
    )
    (net (code "119") (name "unconnected-(J8-Pad34)") (class "Default")
      (node (ref "J8") (pin "34") (pinfunction "34_34") (pintype "passive+no_connect"))
    )
    (net (code "120") (name "unconnected-(J10-MNT-Pad17)") (class "Default")
      (node (ref "J10") (pin "17") (pinfunction "MNT_17") (pintype "passive+no_connect"))
    )
    (net (code "121") (name "unconnected-(J10-MNT-Pad18)") (class "Default")
      (node (ref "J10") (pin "18") (pinfunction "MNT_18") (pintype "passive+no_connect"))
    )
    (net (code "122") (name "unconnected-(J11-MNT-Pad17)") (class "Default")
      (node (ref "J11") (pin "17") (pinfunction "MNT_17") (pintype "passive+no_connect"))
    )
    (net (code "123") (name "unconnected-(J11-MNT-Pad18)") (class "Default")
      (node (ref "J11") (pin "18") (pinfunction "MNT_18") (pintype "passive+no_connect"))
    )
    (net (code "124") (name "unconnected-(J12-MNT-Pad9)") (class "Default")
      (node (ref "J12") (pin "9") (pinfunction "MNT_9") (pintype "passive+no_connect"))
    )
    (net (code "125") (name "unconnected-(J12-MNT-Pad10)") (class "Default")
      (node (ref "J12") (pin "10") (pinfunction "MNT_10") (pintype "passive+no_connect"))
    )
    (net (code "126") (name "unconnected-(NPTH1-H1-Pad1)") (class "Default")
      (node (ref "NPTH1") (pin "1") (pinfunction "H1_1") (pintype "passive+no_connect"))
    )
    (net (code "127") (name "unconnected-(NPTH2-H1-Pad1)") (class "Default")
      (node (ref "NPTH2") (pin "1") (pinfunction "H1_1") (pintype "passive+no_connect"))
    )
    (net (code "128") (name "unconnected-(NPTH3-H1-Pad1)") (class "Default")
      (node (ref "NPTH3") (pin "1") (pinfunction "H1_1") (pintype "passive+no_connect"))
    )
    (net (code "129") (name "unconnected-(NPTH4-H1-Pad1)") (class "Default")
      (node (ref "NPTH4") (pin "1") (pinfunction "H1_1") (pintype "passive+no_connect"))
    )
    (net (code "130") (name "unconnected-(NPTH5-H1-Pad1)") (class "Default")
      (node (ref "NPTH5") (pin "1") (pinfunction "H1_1") (pintype "passive+no_connect"))
    )
    (net (code "131") (name "unconnected-(SW1-Pad1)") (class "Default")
      (node (ref "SW1") (pin "1") (pinfunction "1_1") (pintype "passive+no_connect"))
    )
    (net (code "132") (name "unconnected-(SW1-Pad4)") (class "Default")
      (node (ref "SW1") (pin "4") (pinfunction "4_4") (pintype "passive+no_connect"))
    )
    (net (code "133") (name "unconnected-(U1-IS-Pad4)") (class "Default")
      (node (ref "U1") (pin "4") (pinfunction "IS_4") (pintype "passive+no_connect"))
    )
    (net (code "134") (name "unconnected-(U1-NC1-Pad5)") (class "Default")
      (node (ref "U1") (pin "5") (pinfunction "NC1_5") (pintype "passive"))
    )
    (net (code "135") (name "unconnected-(U1-NC2-Pad6)") (class "Default")
      (node (ref "U1") (pin "6") (pinfunction "NC2_6") (pintype "passive"))
    )
    (net (code "136") (name "unconnected-(U1-NC3-Pad7)") (class "Default")
      (node (ref "U1") (pin "7") (pinfunction "NC3_7") (pintype "passive"))
    )
    (net (code "137") (name "unconnected-(U1-NC4-Pad11)") (class "Default")
      (node (ref "U1") (pin "11") (pinfunction "NC4_11") (pintype "passive"))
    )
  )
)
